# SparkFun_Pi_Wedge_40-Pin_PreAssembled.net
KiCad netlist of a schematic drawn in EAGLE
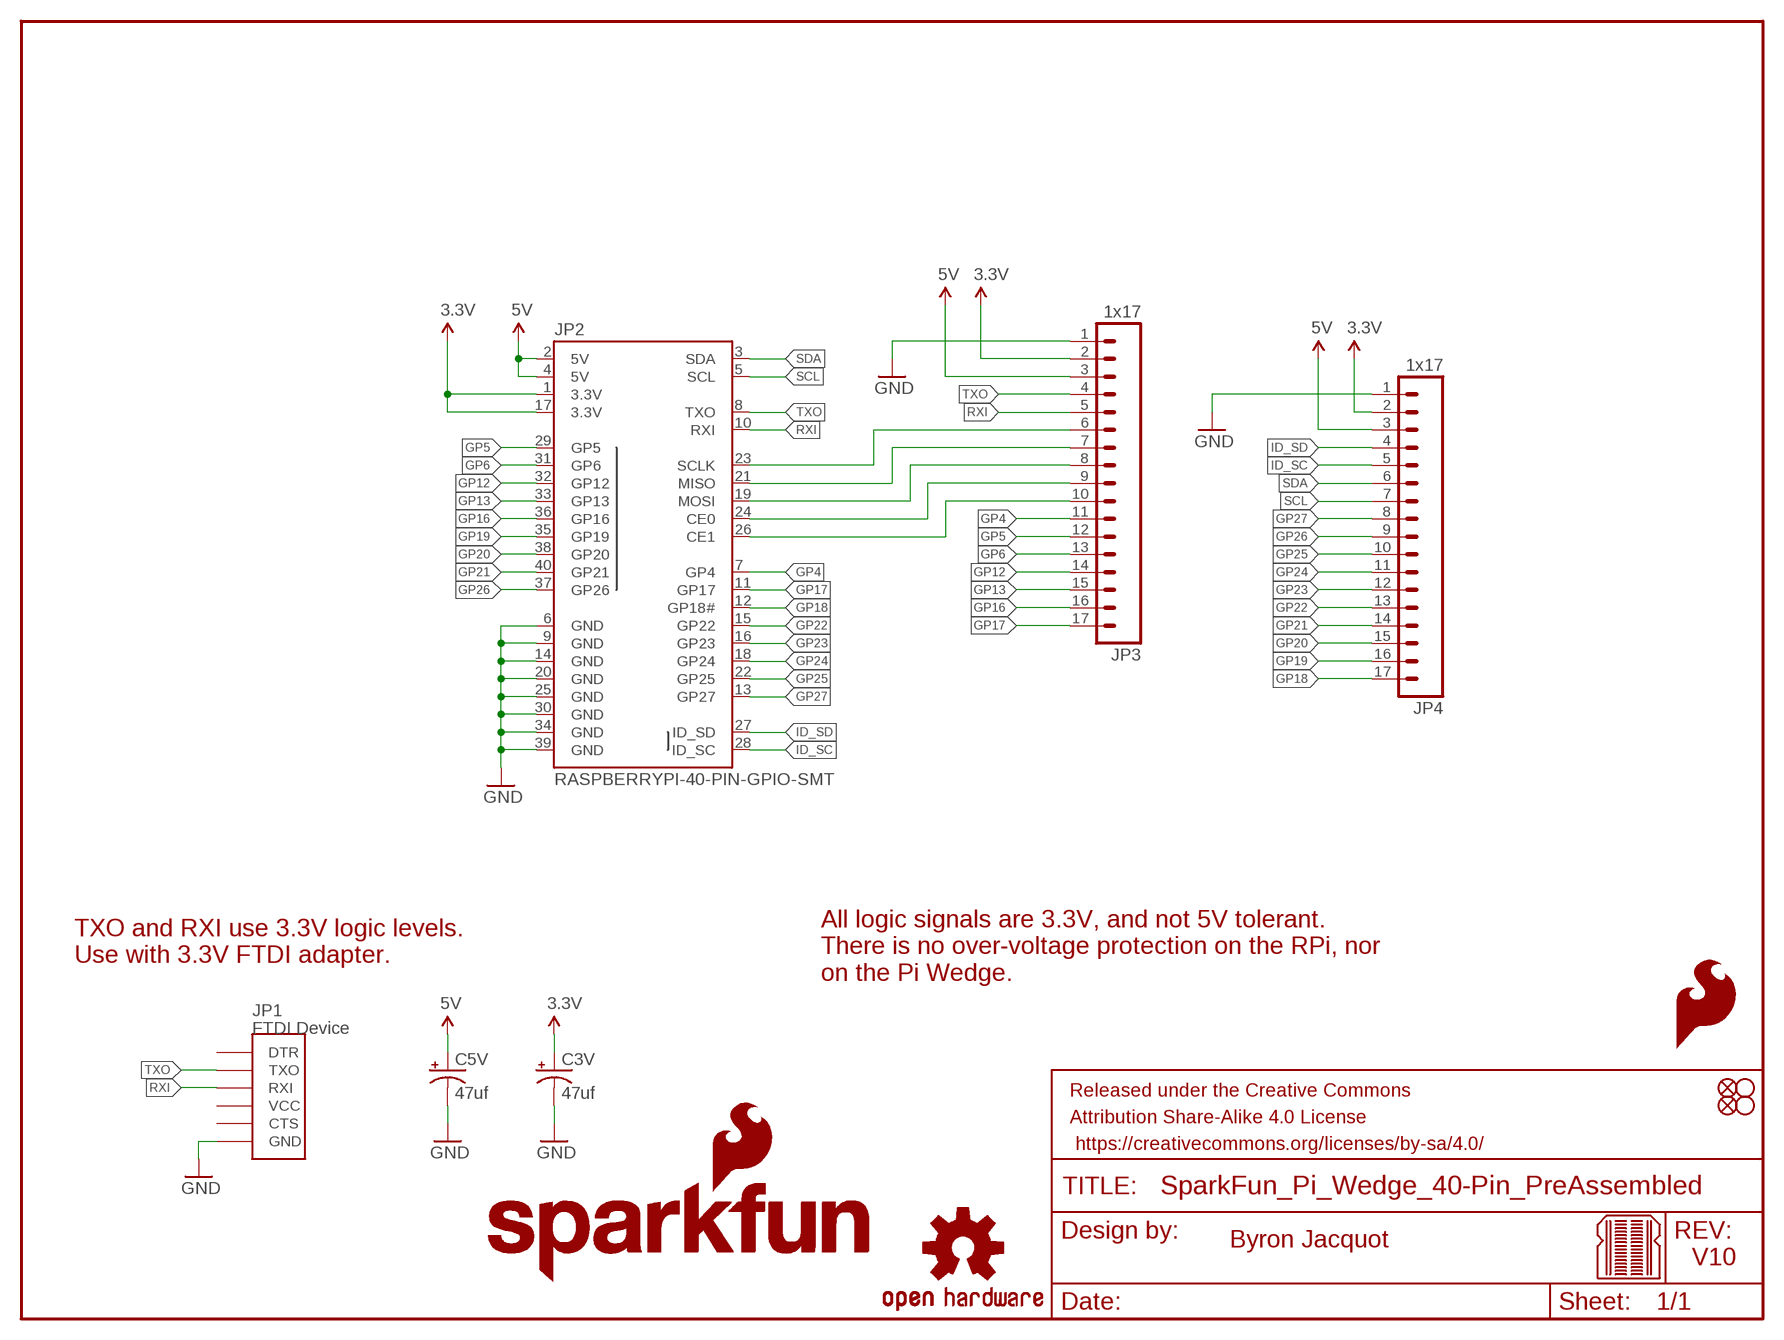
[diagram p0: schematic, sheet 1]

(export (version "E")
  (design (tool "Eeschema 10.0.6"))
  (components
    (comp (ref "C3V")
      (value "47uf")
      (footprint "eagle-import:PANASONIC_D")
      (libsource (lib "eagle-import") (part "47UF-50V-20%(ELECT)"))
    )
    (comp (ref "C5V")
      (value "47uf")
      (footprint "eagle-import:PANASONIC_D")
      (libsource (lib "eagle-import") (part "47UF-50V-20%(ELECT)"))
    )
    (comp (ref "FID1")
      (value "FIDUCIALUFIDUCIAL")
      (footprint "eagle-import:MICRO-FIDUCIAL")
      (libsource (lib "eagle-import") (part "FIDUCIALUFIDUCIAL"))
    )
    (comp (ref "FID2")
      (value "FIDUCIALUFIDUCIAL")
      (footprint "eagle-import:MICRO-FIDUCIAL")
      (libsource (lib "eagle-import") (part "FIDUCIALUFIDUCIAL"))
    )
    (comp (ref "FRAME2")
      (value "FRAME-LETTER")
      (footprint "eagle-import:CREATIVE_COMMONS")
      (libsource (lib "eagle-import") (part "FRAME-LETTER"))
    )
    (comp (ref "JP1")
      (value "FTDI Device")
      (footprint "eagle-import:FTDI_DEVICE_RA_SMT")
      (libsource (lib "eagle-import") (part "FTDI_DEVICERA_SMT"))
    )
    (comp (ref "JP2")
      (value "RASPBERRYPI-40-PIN-GPIO-SMT")
      (footprint "eagle-import:2X20-SHROUDED-SMT")
      (libsource (lib "eagle-import") (part "RASPBERRYPI-40-PIN-GPIO-SMT"))
    )
    (comp (ref "JP3")
      (value "1x17")
      (footprint "eagle-import:1X17_NO_SILK_KIT")
      (libsource (lib "eagle-import") (part "M17KIT"))
    )
    (comp (ref "JP4")
      (value "1x17")
      (footprint "eagle-import:1X17_NO_SILK_KIT")
      (libsource (lib "eagle-import") (part "M17KIT"))
    )
    (comp (ref "LOGO1")
      (value "SFE_LOGO_NAME.2_INCH")
      (footprint "eagle-import:SFE_LOGO_NAME_.2")
      (libsource (lib "eagle-import") (part "SFE_LOGO_NAME.2_INCH"))
    )
    (comp (ref "LOGO2")
      (value "SFE_LOGO_NAME_FLAME.2_INCH")
      (footprint "eagle-import:SFE_LOGO_NAME_FLAME_.2")
      (libsource (lib "eagle-import") (part "SFE_LOGO_NAME_FLAME.2_INCH"))
    )
    (comp (ref "LOGO3")
      (value "SFE_LOGO_FLAME.1_INCH")
      (footprint "eagle-import:SFE_LOGO_FLAME_.1")
      (libsource (lib "eagle-import") (part "SFE_LOGO_FLAME.1_INCH"))
    )
    (comp (ref "LOGO4")
      (value "SFE_LOGO_FLAME.1_INCH")
      (footprint "eagle-import:SFE_LOGO_FLAME_.1")
      (libsource (lib "eagle-import") (part "SFE_LOGO_FLAME.1_INCH"))
    )
    (comp (ref "LOGO5")
      (value "OSHW-LOGOS")
      (footprint "eagle-import:OSHW-LOGO-S")
      (libsource (lib "eagle-import") (part "OSHW-LOGOS"))
    )
    (comp (ref "STANDOFF1")
      (value "STAND-OFF")
      (footprint "eagle-import:STAND-OFF")
      (libsource (lib "eagle-import") (part "STAND-OFF"))
    )
    (comp (ref "STANDOFF2")
      (value "STAND-OFF")
      (footprint "eagle-import:STAND-OFF")
      (libsource (lib "eagle-import") (part "STAND-OFF"))
    )
    (comp (ref "U$2")
      (value "BREADBOARD_PATTERN")
      (footprint "eagle-import:BREADBOARD_SPACING")
      (libsource (lib "eagle-import") (part "BREADBOARD_PATTERN"))
    )
  )
  (nets
    (net (code "1") (name "3.3V") (class "Default")
      (node (ref "C3V") (pin "+") (pinfunction "+_+") (pintype "passive"))
      (node (ref "JP2") (pin "1") (pinfunction "3.3V_1") (pintype "power_in"))
      (node (ref "JP2") (pin "17") (pinfunction "3.3V_17") (pintype "power_in"))
      (node (ref "JP3") (pin "2") (pinfunction "2_2") (pintype "passive"))
      (node (ref "JP4") (pin "2") (pinfunction "2_2") (pintype "passive"))
    )
    (net (code "2") (name "5V") (class "Default")
      (node (ref "C5V") (pin "+") (pinfunction "+_+") (pintype "passive"))
      (node (ref "JP2") (pin "2") (pinfunction "5V_2") (pintype "power_in"))
      (node (ref "JP2") (pin "4") (pinfunction "5V_4") (pintype "power_in"))
      (node (ref "JP3") (pin "3") (pinfunction "3_3") (pintype "passive"))
      (node (ref "JP4") (pin "3") (pinfunction "3_3") (pintype "passive"))
    )
    (net (code "3") (name "GND") (class "Default")
      (node (ref "C3V") (pin "-") (pinfunction "-_-") (pintype "passive"))
      (node (ref "C5V") (pin "-") (pinfunction "-_-") (pintype "passive"))
      (node (ref "JP1") (pin "6") (pinfunction "GND_6") (pintype "bidirectional"))
      (node (ref "JP2") (pin "14") (pinfunction "GND_14") (pintype "power_in"))
      (node (ref "JP2") (pin "20") (pinfunction "GND_20") (pintype "power_in"))
      (node (ref "JP2") (pin "25") (pinfunction "GND_25") (pintype "power_in"))
      (node (ref "JP2") (pin "30") (pinfunction "GND_30") (pintype "power_in"))
      (node (ref "JP2") (pin "34") (pinfunction "GND_34") (pintype "power_in"))
      (node (ref "JP2") (pin "39") (pinfunction "GND_39") (pintype "power_in"))
      (node (ref "JP2") (pin "6") (pinfunction "GND_6") (pintype "power_in"))
      (node (ref "JP2") (pin "9") (pinfunction "GND_9") (pintype "power_in"))
      (node (ref "JP3") (pin "1") (pinfunction "1_1") (pintype "passive"))
      (node (ref "JP4") (pin "1") (pinfunction "1_1") (pintype "passive"))
    )
    (net (code "4") (name "GP4") (class "Default")
      (node (ref "JP2") (pin "7") (pinfunction "GP4_7") (pintype "bidirectional"))
      (node (ref "JP3") (pin "11") (pinfunction "11_11") (pintype "passive"))
    )
    (net (code "5") (name "GP5") (class "Default")
      (node (ref "JP2") (pin "29") (pinfunction "GP5_29") (pintype "bidirectional"))
      (node (ref "JP3") (pin "12") (pinfunction "12_12") (pintype "passive"))
    )
    (net (code "6") (name "GP6") (class "Default")
      (node (ref "JP2") (pin "31") (pinfunction "GP6_31") (pintype "bidirectional"))
      (node (ref "JP3") (pin "13") (pinfunction "13_13") (pintype "passive"))
    )
    (net (code "7") (name "GP12") (class "Default")
      (node (ref "JP2") (pin "32") (pinfunction "GP12_32") (pintype "bidirectional"))
      (node (ref "JP3") (pin "14") (pinfunction "14_14") (pintype "passive"))
    )
    (net (code "8") (name "GP13") (class "Default")
      (node (ref "JP2") (pin "33") (pinfunction "GP13_33") (pintype "bidirectional"))
      (node (ref "JP3") (pin "15") (pinfunction "15_15") (pintype "passive"))
    )
    (net (code "9") (name "GP16") (class "Default")
      (node (ref "JP2") (pin "36") (pinfunction "GP16_36") (pintype "bidirectional"))
      (node (ref "JP3") (pin "16") (pinfunction "16_16") (pintype "passive"))
    )
    (net (code "10") (name "GP17") (class "Default")
      (node (ref "JP2") (pin "11") (pinfunction "GP17_11") (pintype "bidirectional"))
      (node (ref "JP3") (pin "17") (pinfunction "17_17") (pintype "passive"))
    )
    (net (code "11") (name "GP18") (class "Default")
      (node (ref "JP2") (pin "12") (pinfunction "GP18#_12") (pintype "bidirectional"))
      (node (ref "JP4") (pin "17") (pinfunction "17_17") (pintype "passive"))
    )
    (net (code "12") (name "GP19") (class "Default")
      (node (ref "JP2") (pin "35") (pinfunction "GP19_35") (pintype "bidirectional"))
      (node (ref "JP4") (pin "16") (pinfunction "16_16") (pintype "passive"))
    )
    (net (code "13") (name "GP20") (class "Default")
      (node (ref "JP2") (pin "38") (pinfunction "GP20_38") (pintype "bidirectional"))
      (node (ref "JP4") (pin "15") (pinfunction "15_15") (pintype "passive"))
    )
    (net (code "14") (name "GP21") (class "Default")
      (node (ref "JP2") (pin "40") (pinfunction "GP21_40") (pintype "bidirectional"))
      (node (ref "JP4") (pin "14") (pinfunction "14_14") (pintype "passive"))
    )
    (net (code "15") (name "GP22") (class "Default")
      (node (ref "JP2") (pin "15") (pinfunction "GP22_15") (pintype "bidirectional"))
      (node (ref "JP4") (pin "13") (pinfunction "13_13") (pintype "passive"))
    )
    (net (code "16") (name "GP23") (class "Default")
      (node (ref "JP2") (pin "16") (pinfunction "GP23_16") (pintype "bidirectional"))
      (node (ref "JP4") (pin "12") (pinfunction "12_12") (pintype "passive"))
    )
    (net (code "17") (name "GP24") (class "Default")
      (node (ref "JP2") (pin "18") (pinfunction "GP24_18") (pintype "bidirectional"))
      (node (ref "JP4") (pin "11") (pinfunction "11_11") (pintype "passive"))
    )
    (net (code "18") (name "GP25") (class "Default")
      (node (ref "JP2") (pin "22") (pinfunction "GP25_22") (pintype "bidirectional"))
      (node (ref "JP4") (pin "10") (pinfunction "10_10") (pintype "passive"))
    )
    (net (code "19") (name "GP26") (class "Default")
      (node (ref "JP2") (pin "37") (pinfunction "GP26_37") (pintype "bidirectional"))
      (node (ref "JP4") (pin "9") (pinfunction "9_9") (pintype "passive"))
    )
    (net (code "20") (name "GP27") (class "Default")
      (node (ref "JP2") (pin "13") (pinfunction "GP27_13") (pintype "bidirectional"))
      (node (ref "JP4") (pin "8") (pinfunction "8_8") (pintype "passive"))
    )
    (net (code "21") (name "ID_SC") (class "Default")
      (node (ref "JP2") (pin "28") (pinfunction "ID_SC_28") (pintype "bidirectional"))
      (node (ref "JP4") (pin "5") (pinfunction "5_5") (pintype "passive"))
    )
    (net (code "22") (name "ID_SD") (class "Default")
      (node (ref "JP2") (pin "27") (pinfunction "ID_SD_27") (pintype "bidirectional"))
      (node (ref "JP4") (pin "4") (pinfunction "4_4") (pintype "passive"))
    )
    (net (code "23") (name "Net-(JP2-CE0)") (class "Default")
      (node (ref "JP2") (pin "24") (pinfunction "CE0_24") (pintype "output"))
      (node (ref "JP3") (pin "9") (pinfunction "9_9") (pintype "passive"))
    )
    (net (code "24") (name "Net-(JP2-CE1)") (class "Default")
      (node (ref "JP2") (pin "26") (pinfunction "CE1_26") (pintype "output"))
      (node (ref "JP3") (pin "10") (pinfunction "10_10") (pintype "passive"))
    )
    (net (code "25") (name "Net-(JP2-MISO)") (class "Default")
      (node (ref "JP2") (pin "21") (pinfunction "MISO_21") (pintype "input"))
      (node (ref "JP3") (pin "7") (pinfunction "7_7") (pintype "passive"))
    )
    (net (code "26") (name "Net-(JP2-MOSI)") (class "Default")
      (node (ref "JP2") (pin "19") (pinfunction "MOSI_19") (pintype "output"))
      (node (ref "JP3") (pin "8") (pinfunction "8_8") (pintype "passive"))
    )
    (net (code "27") (name "Net-(JP2-SCLK)") (class "Default")
      (node (ref "JP2") (pin "23") (pinfunction "SCLK_23") (pintype "output"))
      (node (ref "JP3") (pin "6") (pinfunction "6_6") (pintype "passive"))
    )
    (net (code "28") (name "RXI") (class "Default")
      (node (ref "JP1") (pin "3") (pinfunction "RXI_3") (pintype "bidirectional"))
      (node (ref "JP2") (pin "10") (pinfunction "RXI_10") (pintype "input"))
      (node (ref "JP3") (pin "5") (pinfunction "5_5") (pintype "passive"))
    )
    (net (code "29") (name "SCL") (class "Default")
      (node (ref "JP2") (pin "5") (pinfunction "SCL_5") (pintype "bidirectional"))
      (node (ref "JP4") (pin "7") (pinfunction "7_7") (pintype "passive"))
    )
    (net (code "30") (name "SDA") (class "Default")
      (node (ref "JP2") (pin "3") (pinfunction "SDA_3") (pintype "bidirectional"))
      (node (ref "JP4") (pin "6") (pinfunction "6_6") (pintype "passive"))
    )
    (net (code "31") (name "TXO") (class "Default")
      (node (ref "JP1") (pin "2") (pinfunction "TXO_2") (pintype "bidirectional"))
      (node (ref "JP2") (pin "8") (pinfunction "TXO_8") (pintype "output"))
      (node (ref "JP3") (pin "4") (pinfunction "4_4") (pintype "passive"))
    )
    (net (code "32") (name "unconnected-(JP1-CTS-Pad5)") (class "Default")
      (node (ref "JP1") (pin "5") (pinfunction "CTS_5") (pintype "bidirectional"))
    )
    (net (code "33") (name "unconnected-(JP1-DTR-Pad1)") (class "Default")
      (node (ref "JP1") (pin "1") (pinfunction "DTR_1") (pintype "bidirectional"))
    )
    (net (code "34") (name "unconnected-(JP1-VCC-Pad4)") (class "Default")
      (node (ref "JP1") (pin "4") (pinfunction "VCC_4") (pintype "bidirectional"))
    )
  )
)
